# esp32-gps-eth-v12exp.net
KiCad netlist of a schematic drawn in EAGLE
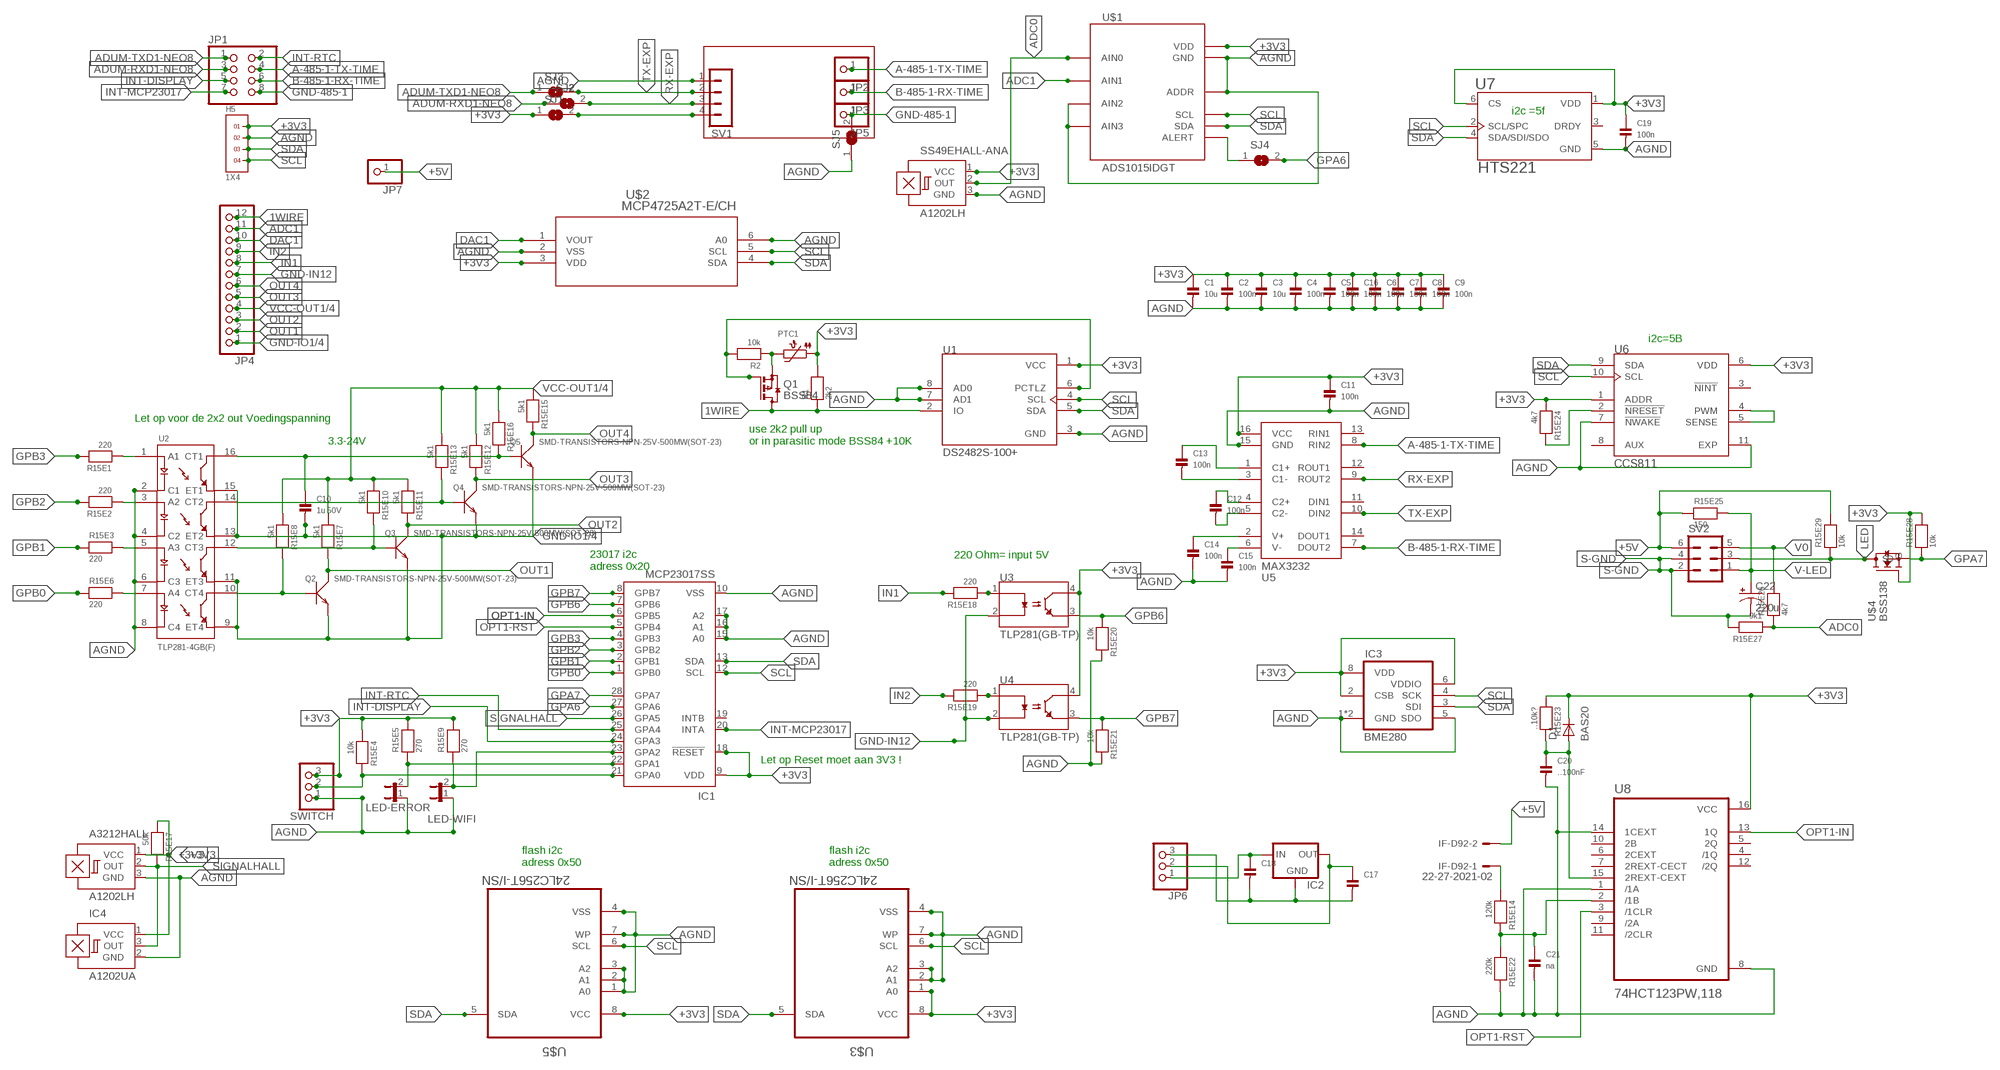
[diagram p0: schematic, sheet 1]

(export (version "E")
  (design (tool "Eeschema 10.0.6"))
  (components
    (comp (ref "A3212HALL")
      (value "A1202LH")
      (footprint "eagle-import:SOT23-W")
      (libsource (lib "eagle-import") (part "A12?LH02"))
    )
    (comp (ref "C1")
      (value "10u")
      (footprint "eagle-import:0805")
      (libsource (lib "eagle-import") (part "CAP_CERAMIC0805"))
    )
    (comp (ref "C2")
      (value "100n")
      (footprint "eagle-import:0805")
      (libsource (lib "eagle-import") (part "CAP_CERAMIC0805"))
    )
    (comp (ref "C3")
      (value "10u")
      (footprint "eagle-import:0805")
      (libsource (lib "eagle-import") (part "CAP_CERAMIC0805"))
    )
    (comp (ref "C4")
      (value "100n")
      (footprint "eagle-import:0805")
      (libsource (lib "eagle-import") (part "CAP_CERAMIC0805"))
    )
    (comp (ref "C5")
      (value "100n")
      (footprint "eagle-import:0805")
      (libsource (lib "eagle-import") (part "CAP_CERAMIC0805"))
    )
    (comp (ref "C6")
      (value "100n")
      (footprint "eagle-import:0805")
      (libsource (lib "eagle-import") (part "CAP_CERAMIC0805"))
    )
    (comp (ref "C7")
      (value "100n")
      (footprint "eagle-import:0805")
      (libsource (lib "eagle-import") (part "CAP_CERAMIC0805"))
    )
    (comp (ref "C8")
      (value "100n")
      (footprint "eagle-import:0805")
      (libsource (lib "eagle-import") (part "CAP_CERAMIC0805"))
    )
    (comp (ref "C9")
      (value "100n")
      (footprint "eagle-import:0805")
      (libsource (lib "eagle-import") (part "CAP_CERAMIC0805"))
    )
    (comp (ref "C10")
      (value "1u 50V")
      (footprint "eagle-import:0805")
      (libsource (lib "eagle-import") (part "CAP_CERAMIC0805"))
    )
    (comp (ref "C11")
      (value "100n")
      (footprint "eagle-import:0805")
      (libsource (lib "eagle-import") (part "CAP_CERAMIC0805"))
    )
    (comp (ref "C12")
      (value "100n")
      (footprint "eagle-import:0805")
      (libsource (lib "eagle-import") (part "CAP_CERAMIC0805"))
    )
    (comp (ref "C13")
      (value "100n")
      (footprint "eagle-import:0805")
      (libsource (lib "eagle-import") (part "CAP_CERAMIC0805"))
    )
    (comp (ref "C14")
      (value "100n")
      (footprint "eagle-import:0805")
      (libsource (lib "eagle-import") (part "CAP_CERAMIC0805"))
    )
    (comp (ref "C15")
      (value "100n")
      (footprint "eagle-import:0805")
      (libsource (lib "eagle-import") (part "CAP_CERAMIC0805"))
    )
    (comp (ref "C16")
      (value "100n")
      (footprint "eagle-import:0805")
      (libsource (lib "eagle-import") (part "CAP_CERAMIC0805"))
    )
    (comp (ref "C17")
      (value "CAP_CERAMIC0805")
      (footprint "eagle-import:0805")
      (libsource (lib "eagle-import") (part "CAP_CERAMIC0805"))
    )
    (comp (ref "C18")
      (value "CAP_CERAMIC0805")
      (footprint "eagle-import:0805")
      (libsource (lib "eagle-import") (part "CAP_CERAMIC0805"))
    )
    (comp (ref "C19")
      (value "100n")
      (footprint "eagle-import:0805")
      (libsource (lib "eagle-import") (part "CAP_CERAMIC0805"))
    )
    (comp (ref "C20")
      (value "..100nF")
      (footprint "eagle-import:0805")
      (libsource (lib "eagle-import") (part "CAP_CERAMIC0805"))
    )
    (comp (ref "C21")
      (value "na")
      (footprint "eagle-import:0805")
      (libsource (lib "eagle-import") (part "CAP_CERAMIC0805"))
    )
    (comp (ref "C22")
      (value "220u")
      (footprint "eagle-import:153CLV-0605")
      (libsource (lib "eagle-import") (part "CPOL-US153CLV-0605"))
    )
    (comp (ref "D1")
      (value "BAS20")
      (footprint "eagle-import:SOT23")
      (fields (field (name "MF") "ON Semiconductor"))
      (libsource (lib "eagle-import") (part "BAS20"))
    )
    (comp (ref "H5")
      (value "1X4")
      (footprint "eagle-import:1X4")
      (libsource (lib "eagle-import") (part "1X4"))
    )
    (comp (ref "IC1")
      (value "MCP23017SS")
      (footprint "eagle-import:SSOP28")
      (fields (field (name "MF") "MICROCHIP") (field (name "MPN") "MCP23017-E/SS"))
      (libsource (lib "eagle-import") (part "MCP23017SS"))
    )
    (comp (ref "IC2")
      (value "LM1117TO263")
      (footprint "eagle-import:TO263")
      (libsource (lib "eagle-import") (part "LM1117TO263"))
    )
    (comp (ref "IC3")
      (value "BME280")
      (footprint "eagle-import:BME280")
      (libsource (lib "eagle-import") (part "BME280"))
    )
    (comp (ref "IC4")
      (value "A1202UA")
      (footprint "eagle-import:SIP3-UA")
      (libsource (lib "eagle-import") (part "A12?UA02"))
    )
    (comp (ref "IF-D92")
      (value "22-27-2021-02")
      (footprint "eagle-import:6410-02")
      (libsource (lib "eagle-import") (part "22-?-0227-2021"))
    )
    (comp (ref "JP1")
      (value "PINHD-2X4")
      (footprint "eagle-import:2X04")
      (libsource (lib "eagle-import") (part "PINHD-2X4"))
    )
    (comp (ref "JP2")
      (value "PINHD-1X1")
      (footprint "eagle-import:1X01")
      (libsource (lib "eagle-import") (part "PINHD-1X1"))
    )
    (comp (ref "JP3")
      (value "PINHD-1X1")
      (footprint "eagle-import:1X01")
      (libsource (lib "eagle-import") (part "PINHD-1X1"))
    )
    (comp (ref "JP4")
      (value "PINHD-1X12")
      (footprint "eagle-import:1X12")
      (libsource (lib "eagle-import") (part "PINHD-1X12"))
    )
    (comp (ref "JP5")
      (value "PINHD-1X1")
      (footprint "eagle-import:1X01")
      (libsource (lib "eagle-import") (part "PINHD-1X1"))
    )
    (comp (ref "JP6")
      (value "PINHD-1X3")
      (footprint "eagle-import:1X03")
      (libsource (lib "eagle-import") (part "PINHD-1X3"))
    )
    (comp (ref "JP7")
      (value "PINHD-1X1")
      (footprint "eagle-import:1X01")
      (libsource (lib "eagle-import") (part "PINHD-1X1"))
    )
    (comp (ref "LED-ERROR")
      (value "JP1E")
      (footprint "eagle-import:JP1")
      (libsource (lib "eagle-import") (part "JP1E"))
    )
    (comp (ref "LED-WIFI")
      (value "JP1E")
      (footprint "eagle-import:JP1")
      (libsource (lib "eagle-import") (part "JP1E"))
    )
    (comp (ref "PTC1")
      (value "PTC1206")
      (footprint "eagle-import:1206")
      (libsource (lib "eagle-import") (part "PTC1206"))
    )
    (comp (ref "Q1")
      (value "BSS84")
      (footprint "eagle-import:SOT23")
      (libsource (lib "eagle-import") (part "BSS84"))
    )
    (comp (ref "Q2")
      (value "SMD-TRANSISTORS-NPN-25V-500MW(SOT-23)")
      (footprint "eagle-import:SOT-23")
      (fields (field (name "MF") "Micro Commercial") (field (name "MP") "S8050"))
      (libsource (lib "eagle-import") (part "SMD-TRANSISTORS-NPN-25V-500MW(SOT-23)"))
    )
    (comp (ref "Q3")
      (value "SMD-TRANSISTORS-NPN-25V-500MW(SOT-23)")
      (footprint "eagle-import:SOT-23")
      (fields (field (name "MF") "Micro Commercial") (field (name "MP") "S8050"))
      (libsource (lib "eagle-import") (part "SMD-TRANSISTORS-NPN-25V-500MW(SOT-23)"))
    )
    (comp (ref "Q4")
      (value "SMD-TRANSISTORS-NPN-25V-500MW(SOT-23)")
      (footprint "eagle-import:SOT-23")
      (fields (field (name "MF") "Micro Commercial") (field (name "MP") "S8050"))
      (libsource (lib "eagle-import") (part "SMD-TRANSISTORS-NPN-25V-500MW(SOT-23)"))
    )
    (comp (ref "Q5")
      (value "SMD-TRANSISTORS-NPN-25V-500MW(SOT-23)")
      (footprint "eagle-import:SOT-23")
      (fields (field (name "MF") "Micro Commercial") (field (name "MP") "S8050"))
      (libsource (lib "eagle-import") (part "SMD-TRANSISTORS-NPN-25V-500MW(SOT-23)"))
    )
    (comp (ref "R1")
      (value "2k2")
      (footprint "eagle-import:0805")
      (libsource (lib "eagle-import") (part "RESISTOR0805"))
    )
    (comp (ref "R2")
      (value "10k")
      (footprint "eagle-import:0805")
      (libsource (lib "eagle-import") (part "RESISTOR0805"))
    )
    (comp (ref "R15E1")
      (value "220")
      (footprint "eagle-import:_0805")
      (libsource (lib "eagle-import") (part "RESISTOR_0805"))
    )
    (comp (ref "R15E2")
      (value "220")
      (footprint "eagle-import:_0805")
      (libsource (lib "eagle-import") (part "RESISTOR_0805"))
    )
    (comp (ref "R15E3")
      (value "220")
      (footprint "eagle-import:_0805")
      (libsource (lib "eagle-import") (part "RESISTOR_0805"))
    )
    (comp (ref "R15E4")
      (value "10k")
      (footprint "eagle-import:_0805")
      (libsource (lib "eagle-import") (part "RESISTOR_0805"))
    )
    (comp (ref "R15E5")
      (value "270")
      (footprint "eagle-import:_0805")
      (libsource (lib "eagle-import") (part "RESISTOR_0805"))
    )
    (comp (ref "R15E6")
      (value "220")
      (footprint "eagle-import:_0805")
      (libsource (lib "eagle-import") (part "RESISTOR_0805"))
    )
    (comp (ref "R15E7")
      (value "5k1")
      (footprint "eagle-import:_0805")
      (libsource (lib "eagle-import") (part "RESISTOR_0805"))
    )
    (comp (ref "R15E8")
      (value "5k1")
      (footprint "eagle-import:_0805")
      (libsource (lib "eagle-import") (part "RESISTOR_0805"))
    )
    (comp (ref "R15E9")
      (value "270")
      (footprint "eagle-import:_0805")
      (libsource (lib "eagle-import") (part "RESISTOR_0805"))
    )
    (comp (ref "R15E10")
      (value "5k1")
      (footprint "eagle-import:_0805")
      (libsource (lib "eagle-import") (part "RESISTOR_0805"))
    )
    (comp (ref "R15E11")
      (value "5k1")
      (footprint "eagle-import:_0805")
      (libsource (lib "eagle-import") (part "RESISTOR_0805"))
    )
    (comp (ref "R15E12")
      (value "5k1")
      (footprint "eagle-import:_0805")
      (libsource (lib "eagle-import") (part "RESISTOR_0805"))
    )
    (comp (ref "R15E13")
      (value "5k1")
      (footprint "eagle-import:_0805")
      (libsource (lib "eagle-import") (part "RESISTOR_0805"))
    )
    (comp (ref "R15E14")
      (value "120k")
      (footprint "eagle-import:_0805")
      (libsource (lib "eagle-import") (part "RESISTOR_0805"))
    )
    (comp (ref "R15E15")
      (value "5k1")
      (footprint "eagle-import:_0805")
      (libsource (lib "eagle-import") (part "RESISTOR_0805"))
    )
    (comp (ref "R15E16")
      (value "5k1")
      (footprint "eagle-import:_0805")
      (libsource (lib "eagle-import") (part "RESISTOR_0805"))
    )
    (comp (ref "R15E17")
      (value "50k")
      (footprint "eagle-import:_0805")
      (libsource (lib "eagle-import") (part "RESISTOR_0805"))
    )
    (comp (ref "R15E18")
      (value "220")
      (footprint "eagle-import:_0805")
      (libsource (lib "eagle-import") (part "RESISTOR_0805"))
    )
    (comp (ref "R15E19")
      (value "220")
      (footprint "eagle-import:_0805")
      (libsource (lib "eagle-import") (part "RESISTOR_0805"))
    )
    (comp (ref "R15E20")
      (value "10k")
      (footprint "eagle-import:_0805")
      (libsource (lib "eagle-import") (part "RESISTOR_0805"))
    )
    (comp (ref "R15E21")
      (value "10k")
      (footprint "eagle-import:_0805")
      (libsource (lib "eagle-import") (part "RESISTOR_0805"))
    )
    (comp (ref "R15E22")
      (value "220k")
      (footprint "eagle-import:_0805")
      (libsource (lib "eagle-import") (part "RESISTOR_0805"))
    )
    (comp (ref "R15E23")
      (value "..10k?")
      (footprint "eagle-import:_0805")
      (libsource (lib "eagle-import") (part "RESISTOR_0805"))
    )
    (comp (ref "R15E24")
      (value "4k7")
      (footprint "eagle-import:_0805")
      (libsource (lib "eagle-import") (part "RESISTOR_0805"))
    )
    (comp (ref "R15E25")
      (value "150")
      (footprint "eagle-import:_0805")
      (libsource (lib "eagle-import") (part "RESISTOR_0805"))
    )
    (comp (ref "R15E26")
      (value "4k7")
      (footprint "eagle-import:_0805")
      (libsource (lib "eagle-import") (part "RESISTOR_0805"))
    )
    (comp (ref "R15E27")
      (value "9k1")
      (footprint "eagle-import:_0805")
      (libsource (lib "eagle-import") (part "RESISTOR_0805"))
    )
    (comp (ref "R15E28")
      (value "10k")
      (footprint "eagle-import:_0805")
      (libsource (lib "eagle-import") (part "RESISTOR_0805"))
    )
    (comp (ref "R15E29")
      (value "10k")
      (footprint "eagle-import:_0805")
      (libsource (lib "eagle-import") (part "RESISTOR_0805"))
    )
    (comp (ref "SJ1") (value "SJ") (footprint "eagle-import:SJ") (libsource (lib "eagle-import") (part "SJ")))
    (comp (ref "SJ2") (value "SJ") (footprint "eagle-import:SJ") (libsource (lib "eagle-import") (part "SJ")))
    (comp (ref "SJ3") (value "SJ") (footprint "eagle-import:SJ") (libsource (lib "eagle-import") (part "SJ")))
    (comp (ref "SJ4") (value "SJ") (footprint "eagle-import:SJ") (libsource (lib "eagle-import") (part "SJ")))
    (comp (ref "SJ5") (value "SJ") (footprint "eagle-import:SJ") (libsource (lib "eagle-import") (part "SJ")))
    (comp (ref "SS49EHALL-ANA")
      (value "A1202LH")
      (footprint "eagle-import:SOT23-W")
      (libsource (lib "eagle-import") (part "A12?LH02"))
    )
    (comp (ref "SV1")
      (value "MA04-1")
      (footprint "eagle-import:MA04-1")
      (libsource (lib "eagle-import") (part "MA04-1"))
    )
    (comp (ref "SV2")
      (value "MA03-2")
      (footprint "eagle-import:MA03-2")
      (libsource (lib "eagle-import") (part "MA03-2"))
    )
    (comp (ref "SWITCH")
      (value "PINHD-1X3")
      (footprint "eagle-import:1X03")
      (libsource (lib "eagle-import") (part "PINHD-1X3"))
    )
    (comp (ref "U$1")
      (value "ADS1015IDGT")
      (footprint "eagle-import:MSOP10_0.5")
      (fields (field (name "MF") "Texas Instruments") (field (name "MP") "ADS1015"))
      (libsource (lib "eagle-import") (part "ADS1015IDGT"))
    )
    (comp (ref "U$2")
      (value "MCP4725A2T-E/CH")
      (footprint "eagle-import:SOT-23-6_MC")
      (fields (field (name "MF") "Microchip"))
      (libsource (lib "eagle-import") (part "MCP4725A2T-E/CH"))
    )
    (comp (ref "U$3")
      (value "24LC256T-I/SN")
      (footprint "eagle-import:SOIC127P600X175-8N")
      (libsource (lib "eagle-import") (part "24LC256T-I/SN"))
    )
    (comp (ref "U$4")
      (value "BSS138")
      (footprint "eagle-import:BSS138")
      (libsource (lib "eagle-import") (part "BSS138"))
    )
    (comp (ref "U$5")
      (value "24LC256T-I/SN")
      (footprint "eagle-import:SOIC127P600X175-8N")
      (libsource (lib "eagle-import") (part "24LC256T-I/SN"))
    )
    (comp (ref "U1")
      (value "DS2482S-100+")
      (footprint "eagle-import:SOIC127P600X175-8N")
      (fields (field (name "MF") "Maxim Integrated"))
      (libsource (lib "eagle-import") (part "DS2482S-100+"))
    )
    (comp (ref "U2")
      (value "TLP281-4GB(F)")
      (footprint "eagle-import:SOIC127P700X210-16N")
      (fields (field (name "MF") "Toshiba") (field (name "MP") "TLP281-4GB_F_"))
      (libsource (lib "eagle-import") (part "TLP281-4GB(F)"))
    )
    (comp (ref "U3")
      (value "TLP281(GB-TP)")
      (footprint "eagle-import:SOIC127P700X210-4N")
      (fields (field (name "MF") "Toshiba Semiconductor") (field (name "MP") "TLP281_GB-TP_"))
      (libsource (lib "eagle-import") (part "TLP281(GB-TP)"))
    )
    (comp (ref "U4")
      (value "TLP281(GB-TP)")
      (footprint "eagle-import:SOIC127P700X210-4N")
      (fields (field (name "MF") "Toshiba Semiconductor") (field (name "MP") "TLP281_GB-TP_"))
      (libsource (lib "eagle-import") (part "TLP281(GB-TP)"))
    )
    (comp (ref "U5")
      (value "MAX3232")
      (footprint "eagle-import:SO16")
      (fields (field (name "MF") "Texas Instruments"))
      (libsource (lib "eagle-import") (part "MAX3232"))
    )
    (comp (ref "U6")
      (value "CCS811")
      (footprint "eagle-import:SON60P270X400X110-11N")
      (fields (field (name "MF") "ams"))
      (libsource (lib "eagle-import") (part "CCS811"))
    )
    (comp (ref "U7")
      (value "HTS221")
      (footprint "eagle-import:XDCR_HTS221")
      (fields (field (name "MF") "STMicroelectronics"))
      (libsource (lib "eagle-import") (part "HTS221"))
    )
    (comp (ref "U8")
      (value "74HCT123PW,118")
      (footprint "eagle-import:SOP65P640X110-16N")
      (fields (field (name "MF") "Nexperia USA"))
      (libsource (lib "eagle-import") (part "74HCT123PW,118"))
    )
  )
  (nets
    (net (code "1") (name "+3V3") (class "Default")
      (node (ref "A3212HALL") (pin "1") (pinfunction "VCC_1") (pintype "power_in"))
      (node (ref "C1") (pin "1") (pinfunction "P$1_1") (pintype "passive"))
      (node (ref "C11") (pin "1") (pinfunction "P$1_1") (pintype "passive"))
      (node (ref "C16") (pin "1") (pinfunction "P$1_1") (pintype "passive"))
      (node (ref "C19") (pin "1") (pinfunction "P$1_1") (pintype "passive"))
      (node (ref "C2") (pin "1") (pinfunction "P$1_1") (pintype "passive"))
      (node (ref "C3") (pin "1") (pinfunction "P$1_1") (pintype "passive"))
      (node (ref "C4") (pin "1") (pinfunction "P$1_1") (pintype "passive"))
      (node (ref "C5") (pin "1") (pinfunction "P$1_1") (pintype "passive"))
      (node (ref "C6") (pin "1") (pinfunction "P$1_1") (pintype "passive"))
      (node (ref "C7") (pin "1") (pinfunction "P$1_1") (pintype "passive"))
      (node (ref "C8") (pin "1") (pinfunction "P$1_1") (pintype "passive"))
      (node (ref "C9") (pin "1") (pinfunction "P$1_1") (pintype "passive"))
      (node (ref "D1") (pin "3") (pinfunction "K_3") (pintype "passive"))
      (node (ref "H5") (pin "1") (pinfunction "1_1") (pintype "bidirectional"))
      (node (ref "IC1") (pin "18") (pinfunction "~{RESET}_18") (pintype "input"))
      (node (ref "IC1") (pin "9") (pinfunction "VDD_9") (pintype "power_in"))
      (node (ref "IC3") (pin "2") (pinfunction "CSB_2") (pintype "input"))
      (node (ref "IC3") (pin "6") (pinfunction "VDDIO_6") (pintype "power_in"))
      (node (ref "IC3") (pin "8") (pinfunction "VDD_8") (pintype "power_in"))
      (node (ref "IC4") (pin "1") (pinfunction "VCC_1") (pintype "power_in"))
      (node (ref "PTC1") (pin "1") (pinfunction "1_1") (pintype "passive"))
      (node (ref "R1") (pin "2") (pinfunction "2_2") (pintype "passive"))
      (node (ref "R15E17") (pin "1") (pinfunction "1_1") (pintype "passive"))
      (node (ref "R15E23") (pin "1") (pinfunction "1_1") (pintype "passive"))
      (node (ref "R15E24") (pin "1") (pinfunction "1_1") (pintype "passive"))
      (node (ref "R15E28") (pin "2") (pinfunction "2_2") (pintype "passive"))
      (node (ref "R15E4") (pin "1") (pinfunction "1_1") (pintype "passive"))
      (node (ref "R15E5") (pin "2") (pinfunction "2_2") (pintype "passive"))
      (node (ref "R15E9") (pin "2") (pinfunction "2_2") (pintype "passive"))
      (node (ref "SJ1") (pin "1") (pinfunction "1_1") (pintype "passive"))
      (node (ref "SS49EHALL-ANA") (pin "1") (pinfunction "VCC_1") (pintype "power_in"))
      (node (ref "SWITCH") (pin "3") (pinfunction "3_3") (pintype "passive"))
      (node (ref "U$1") (pin "8") (pinfunction "VDD_8") (pintype "power_in"))
      (node (ref "U$2") (pin "3") (pinfunction "VDD_3") (pintype "passive"))
      (node (ref "U$3") (pin "1") (pinfunction "A0_1") (pintype "input"))
      (node (ref "U$3") (pin "8") (pinfunction "VCC_8") (pintype "power_in"))
      (node (ref "U$4") (pin "G") (pinfunction "G_G") (pintype "passive"))
      (node (ref "U$5") (pin "8") (pinfunction "VCC_8") (pintype "power_in"))
      (node (ref "U1") (pin "1") (pinfunction "VCC_1") (pintype "power_in"))
      (node (ref "U3") (pin "4") (pinfunction "COLLECTOR_4") (pintype "passive"))
      (node (ref "U4") (pin "4") (pinfunction "COLLECTOR_4") (pintype "passive"))
      (node (ref "U5") (pin "16") (pinfunction "VCC_16") (pintype "passive"))
      (node (ref "U6") (pin "1") (pinfunction "ADDR_1") (pintype "input"))
      (node (ref "U6") (pin "6") (pinfunction "VDD_6") (pintype "power_in"))
      (node (ref "U7") (pin "1") (pinfunction "VDD_1") (pintype "power_in"))
      (node (ref "U7") (pin "6") (pinfunction "CS_6") (pintype "input"))
      (node (ref "U8") (pin "16") (pinfunction "VCC_16") (pintype "power_in"))
    )
    (net (code "2") (name "+5V") (class "Default")
      (node (ref "IF-D92") (pin "2") (pinfunction "S_2") (pintype "passive"))
      (node (ref "JP7") (pin "1") (pinfunction "1_1") (pintype "passive"))
      (node (ref "R15E25") (pin "1") (pinfunction "1_1") (pintype "passive"))
      (node (ref "R15E29") (pin "2") (pinfunction "2_2") (pintype "passive"))
      (node (ref "SV2") (pin "6") (pinfunction "6_6") (pintype "passive"))
    )
    (net (code "3") (name "1WIRE") (class "Default")
      (node (ref "JP4") (pin "12") (pinfunction "12_12") (pintype "passive"))
      (node (ref "Q1") (pin "3") (pinfunction "D_3") (pintype "passive"))
      (node (ref "R1") (pin "1") (pinfunction "1_1") (pintype "passive"))
      (node (ref "U1") (pin "2") (pinfunction "IO_2") (pintype "bidirectional"))
    )
    (net (code "4") (name "A-485-1-TX-TIME") (class "Default")
      (node (ref "JP1") (pin "4") (pinfunction "4_4") (pintype "passive"))
      (node (ref "JP2") (pin "1") (pinfunction "1_1") (pintype "passive"))
      (node (ref "U5") (pin "8") (pinfunction "RIN2_8") (pintype "input"))
    )
    (net (code "5") (name "ADC0") (class "Default")
      (node (ref "R15E26") (pin "1") (pinfunction "1_1") (pintype "passive"))
      (node (ref "R15E27") (pin "1") (pinfunction "1_1") (pintype "passive"))
      (node (ref "SS49EHALL-ANA") (pin "2") (pinfunction "OUT_2") (pintype "output"))
      (node (ref "U$1") (pin "4") (pinfunction "AIN0_4") (pintype "input"))
    )
    (net (code "6") (name "ADC1") (class "Default")
      (node (ref "JP4") (pin "11") (pinfunction "11_11") (pintype "passive"))
      (node (ref "U$1") (pin "5") (pinfunction "AIN1_5") (pintype "input"))
    )
    (net (code "7") (name "ADUM-RXD1-NEO8") (class "Default")
      (node (ref "JP1") (pin "3") (pinfunction "3_3") (pintype "passive"))
      (node (ref "SJ2") (pin "1") (pinfunction "1_1") (pintype "passive"))
    )
    (net (code "8") (name "ADUM-TXD1-NEO8") (class "Default")
      (node (ref "JP1") (pin "1") (pinfunction "1_1") (pintype "passive"))
      (node (ref "SJ3") (pin "1") (pinfunction "1_1") (pintype "passive"))
    )
    (net (code "9") (name "AGND") (class "Default")
      (node (ref "A3212HALL") (pin "3") (pinfunction "GND_3") (pintype "power_in"))
      (node (ref "C1") (pin "2") (pinfunction "P$2_2") (pintype "passive"))
      (node (ref "C11") (pin "2") (pinfunction "P$2_2") (pintype "passive"))
      (node (ref "C14") (pin "2") (pinfunction "P$2_2") (pintype "passive"))
      (node (ref "C15") (pin "2") (pinfunction "P$2_2") (pintype "passive"))
      (node (ref "C16") (pin "2") (pinfunction "P$2_2") (pintype "passive"))
      (node (ref "C19") (pin "2") (pinfunction "P$2_2") (pintype "passive"))
      (node (ref "C2") (pin "2") (pinfunction "P$2_2") (pintype "passive"))
      (node (ref "C20") (pin "2") (pinfunction "P$2_2") (pintype "passive"))
      (node (ref "C21") (pin "2") (pinfunction "P$2_2") (pintype "passive"))
      (node (ref "C3") (pin "2") (pinfunction "P$2_2") (pintype "passive"))
      (node (ref "C4") (pin "2") (pinfunction "P$2_2") (pintype "passive"))
      (node (ref "C5") (pin "2") (pinfunction "P$2_2") (pintype "passive"))
      (node (ref "C6") (pin "2") (pinfunction "P$2_2") (pintype "passive"))
      (node (ref "C7") (pin "2") (pinfunction "P$2_2") (pintype "passive"))
      (node (ref "C8") (pin "2") (pinfunction "P$2_2") (pintype "passive"))
      (node (ref "C9") (pin "2") (pinfunction "P$2_2") (pintype "passive"))
      (node (ref "H5") (pin "2") (pinfunction "2_2") (pintype "bidirectional"))
      (node (ref "IC1") (pin "10") (pinfunction "VSS_10") (pintype "power_in"))
      (node (ref "IC1") (pin "15") (pinfunction "A0_15") (pintype "input"))
      (node (ref "IC1") (pin "16") (pinfunction "A1_16") (pintype "input"))
      (node (ref "IC1") (pin "17") (pinfunction "A2_17") (pintype "input"))
      (node (ref "IC3") (pin "1") (pinfunction "GND_1") (pintype "power_in"))
      (node (ref "IC3") (pin "5") (pinfunction "SDO_5") (pintype "input"))
      (node (ref "IC3") (pin "7") (pinfunction "GND_7") (pintype "power_in"))
      (node (ref "IC4") (pin "2") (pinfunction "GND_2") (pintype "power_in"))
      (node (ref "LED-ERROR") (pin "1") (pinfunction "1_1") (pintype "passive"))
      (node (ref "LED-WIFI") (pin "1") (pinfunction "1_1") (pintype "passive"))
      (node (ref "R15E20") (pin "2") (pinfunction "2_2") (pintype "passive"))
      (node (ref "R15E21") (pin "2") (pinfunction "2_2") (pintype "passive"))
      (node (ref "R15E22") (pin "2") (pinfunction "2_2") (pintype "passive"))
      (node (ref "SJ5") (pin "1") (pinfunction "1_1") (pintype "passive"))
      (node (ref "SS49EHALL-ANA") (pin "3") (pinfunction "GND_3") (pintype "power_in"))
      (node (ref "SV1") (pin "1") (pinfunction "1_1") (pintype "passive"))
      (node (ref "SWITCH") (pin "1") (pinfunction "1_1") (pintype "passive"))
      (node (ref "U$1") (pin "1") (pinfunction "ADDR_1") (pintype "input"))
      (node (ref "U$1") (pin "3") (pinfunction "GND_3") (pintype "power_in"))
      (node (ref "U$1") (pin "6") (pinfunction "AIN2_6") (pintype "input"))
      (node (ref "U$1") (pin "7") (pinfunction "AIN3_7") (pintype "input"))
      (node (ref "U$2") (pin "2") (pinfunction "VSS_2") (pintype "passive"))
      (node (ref "U$2") (pin "6") (pinfunction "A0_6") (pintype "passive"))
      (node (ref "U$3") (pin "2") (pinfunction "A1_2") (pintype "input"))
      (node (ref "U$3") (pin "3") (pinfunction "A2_3") (pintype "input"))
      (node (ref "U$3") (pin "4") (pinfunction "VSS_4") (pintype "passive"))
      (node (ref "U$3") (pin "7") (pinfunction "WP_7") (pintype "input"))
      (node (ref "U$5") (pin "1") (pinfunction "A0_1") (pintype "input"))
      (node (ref "U$5") (pin "2") (pinfunction "A1_2") (pintype "input"))
      (node (ref "U$5") (pin "3") (pinfunction "A2_3") (pintype "input"))
      (node (ref "U$5") (pin "4") (pinfunction "VSS_4") (pintype "passive"))
      (node (ref "U$5") (pin "7") (pinfunction "WP_7") (pintype "input"))
      (node (ref "U1") (pin "3") (pinfunction "GND_3") (pintype "power_in"))
      (node (ref "U1") (pin "7") (pinfunction "AD1_7") (pintype "input"))
      (node (ref "U1") (pin "8") (pinfunction "AD0_8") (pintype "input"))
      (node (ref "U2") (pin "2") (pinfunction "C1_2") (pintype "passive"))
      (node (ref "U2") (pin "4") (pinfunction "C2_4") (pintype "passive"))
      (node (ref "U2") (pin "6") (pinfunction "C3_6") (pintype "passive"))
      (node (ref "U2") (pin "8") (pinfunction "C4_8") (pintype "passive"))
      (node (ref "U5") (pin "15") (pinfunction "GND_15") (pintype "passive"))
      (node (ref "U6") (pin "11") (pinfunction "EXP_11") (pintype "power_in"))
      (node (ref "U6") (pin "7") (pinfunction "~{NWAKE}_7") (pintype "input"))
      (node (ref "U7") (pin "5") (pinfunction "GND_5") (pintype "power_in"))
      (node (ref "U8") (pin "1") (pinfunction "/1A_1") (pintype "input"))
      (node (ref "U8") (pin "14") (pinfunction "1CEXT_14") (pintype "input"))
      (node (ref "U8") (pin "8") (pinfunction "GND_8") (pintype "power_in"))
    )
    (net (code "10") (name "B-485-1-RX-TIME") (class "Default")
      (node (ref "JP1") (pin "6") (pinfunction "6_6") (pintype "passive"))
      (node (ref "JP3") (pin "1") (pinfunction "1_1") (pintype "passive"))
      (node (ref "U5") (pin "7") (pinfunction "DOUT2_7") (pintype "output"))
    )
    (net (code "11") (name "DAC1") (class "Default")
      (node (ref "JP4") (pin "10") (pinfunction "10_10") (pintype "passive"))
      (node (ref "U$2") (pin "1") (pinfunction "VOUT_1") (pintype "passive"))
    )
    (net (code "12") (name "GND-485-1") (class "Default")
      (node (ref "JP1") (pin "8") (pinfunction "8_8") (pintype "passive"))
      (node (ref "JP5") (pin "1") (pinfunction "1_1") (pintype "passive"))
      (node (ref "SJ5") (pin "2") (pinfunction "2_2") (pintype "passive"))
    )
    (net (code "13") (name "GND-IN12") (class "Default")
      (node (ref "JP4") (pin "7") (pinfunction "7_7") (pintype "passive"))
      (node (ref "U3") (pin "2") (pinfunction "CATHODE_2") (pintype "passive"))
      (node (ref "U4") (pin "2") (pinfunction "CATHODE_2") (pintype "passive"))
    )
    (net (code "14") (name "GND-IO1{slash}4") (class "Default")
      (node (ref "C10") (pin "2") (pinfunction "P$2_2") (pintype "passive"))
      (node (ref "JP4") (pin "1") (pinfunction "1_1") (pintype "passive"))
      (node (ref "Q2") (pin "2") (pinfunction "E_2") (pintype "passive"))
      (node (ref "Q3") (pin "2") (pinfunction "E_2") (pintype "passive"))
      (node (ref "Q4") (pin "2") (pinfunction "E_2") (pintype "passive"))
      (node (ref "Q5") (pin "2") (pinfunction "E_2") (pintype "passive"))
      (node (ref "U2") (pin "11") (pinfunction "ET3_11") (pintype "passive"))
      (node (ref "U2") (pin "13") (pinfunction "ET2_13") (pintype "passive"))
      (node (ref "U2") (pin "15") (pinfunction "ET1_15") (pintype "passive"))
      (node (ref "U2") (pin "9") (pinfunction "ET4_9") (pintype "passive"))
    )
    (net (code "15") (name "GPA6") (class "Default")
      (node (ref "IC1") (pin "27") (pinfunction "GPA6_27") (pintype "bidirectional"))
      (node (ref "SJ4") (pin "2") (pinfunction "2_2") (pintype "passive"))
    )
    (net (code "16") (name "GPA7") (class "Default")
      (node (ref "IC1") (pin "28") (pinfunction "GPA7_28") (pintype "bidirectional"))
      (node (ref "R15E28") (pin "1") (pinfunction "1_1") (pintype "passive"))
      (node (ref "U$4") (pin "S") (pinfunction "S_S") (pintype "passive"))
    )
    (net (code "17") (name "GPB0") (class "Default")
      (node (ref "IC1") (pin "1") (pinfunction "GPB0_1") (pintype "bidirectional"))
      (node (ref "R15E6") (pin "1") (pinfunction "1_1") (pintype "passive"))
    )
    (net (code "18") (name "GPB1") (class "Default")
      (node (ref "IC1") (pin "2") (pinfunction "GPB1_2") (pintype "bidirectional"))
      (node (ref "R15E3") (pin "1") (pinfunction "1_1") (pintype "passive"))
    )
    (net (code "19") (name "GPB2") (class "Default")
      (node (ref "IC1") (pin "3") (pinfunction "GPB2_3") (pintype "bidirectional"))
      (node (ref "R15E2") (pin "2") (pinfunction "2_2") (pintype "passive"))
    )
    (net (code "20") (name "GPB3") (class "Default")
      (node (ref "IC1") (pin "4") (pinfunction "GPB3_4") (pintype "bidirectional"))
      (node (ref "R15E1") (pin "2") (pinfunction "2_2") (pintype "passive"))
    )
    (net (code "21") (name "GPB6") (class "Default")
      (node (ref "IC1") (pin "7") (pinfunction "GPB6_7") (pintype "bidirectional"))
      (node (ref "R15E20") (pin "1") (pinfunction "1_1") (pintype "passive"))
      (node (ref "U3") (pin "3") (pinfunction "EMITTER_3") (pintype "passive"))
    )
    (net (code "22") (name "GPB7") (class "Default")
      (node (ref "IC1") (pin "8") (pinfunction "GPB7_8") (pintype "bidirectional"))
      (node (ref "R15E21") (pin "1") (pinfunction "1_1") (pintype "passive"))
      (node (ref "U4") (pin "3") (pinfunction "EMITTER_3") (pintype "passive"))
    )
    (net (code "23") (name "IN1") (class "Default")
      (node (ref "JP4") (pin "8") (pinfunction "8_8") (pintype "passive"))
      (node (ref "R15E18") (pin "2") (pinfunction "2_2") (pintype "passive"))
    )
    (net (code "24") (name "IN2") (class "Default")
      (node (ref "JP4") (pin "9") (pinfunction "9_9") (pintype "passive"))
      (node (ref "R15E19") (pin "2") (pinfunction "2_2") (pintype "passive"))
    )
    (net (code "25") (name "INT-DISPLAY") (class "Default")
      (node (ref "IC1") (pin "24") (pinfunction "GPA3_24") (pintype "bidirectional"))
      (node (ref "JP1") (pin "5") (pinfunction "5_5") (pintype "passive"))
    )
    (net (code "26") (name "INT-MCP23017") (class "Default")
      (node (ref "IC1") (pin "20") (pinfunction "INTA_20") (pintype "output"))
      (node (ref "JP1") (pin "7") (pinfunction "7_7") (pintype "passive"))
    )
    (net (code "27") (name "INT-RTC") (class "Default")
      (node (ref "IC1") (pin "25") (pinfunction "GPA4_25") (pintype "bidirectional"))
      (node (ref "JP1") (pin "2") (pinfunction "2_2") (pintype "passive"))
    )
    (net (code "28") (name "LED") (class "Default")
      (node (ref "R15E29") (pin "1") (pinfunction "1_1") (pintype "passive"))
      (node (ref "SV2") (pin "3") (pinfunction "3_3") (pintype "passive"))
      (node (ref "U$4") (pin "D") (pinfunction "D_D") (pintype "passive"))
    )
    (net (code "29") (name "Net-(C10-P$1)") (class "Default")
      (node (ref "C10") (pin "1") (pinfunction "P$1_1") (pintype "passive"))
      (node (ref "Q5") (pin "1") (pinfunction "B_1") (pintype "passive"))
      (node (ref "R15E16") (pin "2") (pinfunction "2_2") (pintype "passive"))
      (node (ref "U2") (pin "16") (pinfunction "CT1_16") (pintype "passive"))
    )
    (net (code "30") (name "Net-(C12-P$1)") (class "Default")
      (node (ref "C12") (pin "1") (pinfunction "P$1_1") (pintype "passive"))
      (node (ref "U5") (pin "4") (pinfunction "C2+_4") (pintype "passive"))
    )
    (net (code "31") (name "Net-(C12-P$2)") (class "Default")
      (node (ref "C12") (pin "2") (pinfunction "P$2_2") (pintype "passive"))
      (node (ref "U5") (pin "5") (pinfunction "C2-_5") (pintype "passive"))
    )
    (net (code "32") (name "Net-(C13-P$1)") (class "Default")
      (node (ref "C13") (pin "1") (pinfunction "P$1_1") (pintype "passive"))
      (node (ref "U5") (pin "1") (pinfunction "C1+_1") (pintype "passive"))
    )
    (net (code "33") (name "Net-(C13-P$2)") (class "Default")
      (node (ref "C13") (pin "2") (pinfunction "P$2_2") (pintype "passive"))
      (node (ref "U5") (pin "3") (pinfunction "C1-_3") (pintype "passive"))
    )
    (net (code "34") (name "Net-(C14-P$1)") (class "Default")
      (node (ref "C14") (pin "1") (pinfunction "P$1_1") (pintype "passive"))
      (node (ref "U5") (pin "2") (pinfunction "V+_2") (pintype "output"))
    )
    (net (code "35") (name "Net-(C15-P$1)") (class "Default")
      (node (ref "C15") (pin "1") (pinfunction "P$1_1") (pintype "passive"))
      (node (ref "U5") (pin "6") (pinfunction "V-_6") (pintype "output"))
    )
    (net (code "36") (name "Net-(C17-P$1)") (class "Default")
      (node (ref "C17") (pin "1") (pinfunction "P$1_1") (pintype "passive"))
      (node (ref "IC2") (pin "2") (pinfunction "OUT_2") (pintype "passive"))
      (node (ref "JP6") (pin "2") (pinfunction "2_2") (pintype "passive"))
    )
    (net (code "37") (name "Net-(C17-P$2)") (class "Default")
      (node (ref "C17") (pin "2") (pinfunction "P$2_2") (pintype "passive"))
      (node (ref "C18") (pin "2") (pinfunction "P$2_2") (pintype "passive"))
      (node (ref "IC2") (pin "1") (pinfunction "GND_1") (pintype "input"))
      (node (ref "JP6") (pin "3") (pinfunction "3_3") (pintype "passive"))
    )
    (net (code "38") (name "Net-(C18-P$1)") (class "Default")
      (node (ref "C18") (pin "1") (pinfunction "P$1_1") (pintype "passive"))
      (node (ref "IC2") (pin "3") (pinfunction "IN_3") (pintype "input"))
      (node (ref "JP6") (pin "1") (pinfunction "1_1") (pintype "passive"))
    )
    (net (code "39") (name "Net-(C20-P$1)") (class "Default")
      (node (ref "C20") (pin "1") (pinfunction "P$1_1") (pintype "passive"))
      (node (ref "D1") (pin "1") (pinfunction "A_1") (pintype "passive"))
      (node (ref "R15E23") (pin "2") (pinfunction "2_2") (pintype "passive"))
      (node (ref "U8") (pin "15") (pinfunction "2REXT-CEXT_15") (pintype "input"))
    )
    (net (code "40") (name "Net-(C21-P$1)") (class "Default")
      (node (ref "C21") (pin "1") (pinfunction "P$1_1") (pintype "passive"))
      (node (ref "R15E14") (pin "2") (pinfunction "2_2") (pintype "passive"))
      (node (ref "R15E22") (pin "1") (pinfunction "1_1") (pintype "passive"))
      (node (ref "U8") (pin "2") (pinfunction "/1B_2") (pintype "input"))
    )
    (net (code "41") (name "Net-(IC1-GPA0)") (class "Default")
      (node (ref "IC1") (pin "21") (pinfunction "GPA0_21") (pintype "bidirectional"))
      (node (ref "R15E4") (pin "2") (pinfunction "2_2") (pintype "passive"))
      (node (ref "SWITCH") (pin "2") (pinfunction "2_2") (pintype "passive"))
    )
    (net (code "42") (name "Net-(IC1-GPA1)") (class "Default")
      (node (ref "IC1") (pin "22") (pinfunction "GPA1_22") (pintype "bidirectional"))
      (node (ref "LED-ERROR") (pin "2") (pinfunction "2_2") (pintype "passive"))
      (node (ref "R15E5") (pin "1") (pinfunction "1_1") (pintype "passive"))
    )
    (net (code "43") (name "Net-(IC1-GPA2)") (class "Default")
      (node (ref "IC1") (pin "23") (pinfunction "GPA2_23") (pintype "bidirectional"))
      (node (ref "LED-WIFI") (pin "2") (pinfunction "2_2") (pintype "passive"))
      (node (ref "R15E9") (pin "1") (pinfunction "1_1") (pintype "passive"))
    )
    (net (code "44") (name "Net-(IF-D92A-S)") (class "Default")
      (node (ref "IF-D92") (pin "1") (pinfunction "S_1") (pintype "passive"))
      (node (ref "R15E14") (pin "1") (pinfunction "1_1") (pintype "passive"))
    )
    (net (code "45") (name "Net-(Q1-G)") (class "Default")
      (node (ref "Q1") (pin "1") (pinfunction "G_1") (pintype "passive"))
      (node (ref "R2") (pin "2") (pinfunction "2_2") (pintype "passive"))
      (node (ref "U1") (pin "6") (pinfunction "PCTLZ_6") (pintype "output"))
    )
    (net (code "46") (name "Net-(Q1-S)") (class "Default")
      (node (ref "PTC1") (pin "2") (pinfunction "2_2") (pintype "passive"))
      (node (ref "Q1") (pin "2") (pinfunction "S_2") (pintype "passive"))
      (node (ref "R2") (pin "1") (pinfunction "1_1") (pintype "passive"))
    )
    (net (code "47") (name "Net-(Q2-B)") (class "Default")
      (node (ref "Q2") (pin "1") (pinfunction "B_1") (pintype "passive"))
      (node (ref "R15E8") (pin "2") (pinfunction "2_2") (pintype "passive"))
      (node (ref "U2") (pin "10") (pinfunction "CT4_10") (pintype "passive"))
    )
    (net (code "48") (name "Net-(Q3-B)") (class "Default")
      (node (ref "Q3") (pin "1") (pinfunction "B_1") (pintype "passive"))
      (node (ref "R15E10") (pin "2") (pinfunction "2_2") (pintype "passive"))
      (node (ref "U2") (pin "12") (pinfunction "CT3_12") (pintype "passive"))
    )
    (net (code "49") (name "Net-(Q4-B)") (class "Default")
      (node (ref "Q4") (pin "1") (pinfunction "B_1") (pintype "passive"))
      (node (ref "R15E13") (pin "2") (pinfunction "2_2") (pintype "passive"))
      (node (ref "U2") (pin "14") (pinfunction "CT2_14") (pintype "passive"))
    )
    (net (code "50") (name "Net-(SJ1-Pad2)") (class "Default")
      (node (ref "SJ1") (pin "2") (pinfunction "2_2") (pintype "passive"))
      (node (ref "SV1") (pin "4") (pinfunction "4_4") (pintype "passive"))
    )
    (net (code "51") (name "Net-(U$1-ALERT)") (class "Default")
      (node (ref "SJ4") (pin "1") (pinfunction "1_1") (pintype "passive"))
      (node (ref "U$1") (pin "2") (pinfunction "ALERT_2") (pintype "output"))
    )
    (net (code "52") (name "Net-(U2-A1)") (class "Default")
      (node (ref "R15E1") (pin "1") (pinfunction "1_1") (pintype "passive"))
      (node (ref "U2") (pin "1") (pinfunction "A1_1") (pintype "passive"))
    )
    (net (code "53") (name "Net-(U2-A2)") (class "Default")
      (node (ref "R15E2") (pin "1") (pinfunction "1_1") (pintype "passive"))
      (node (ref "U2") (pin "3") (pinfunction "A2_3") (pintype "passive"))
    )
    (net (code "54") (name "Net-(U2-A3)") (class "Default")
      (node (ref "R15E3") (pin "2") (pinfunction "2_2") (pintype "passive"))
      (node (ref "U2") (pin "5") (pinfunction "A3_5") (pintype "passive"))
    )
    (net (code "55") (name "Net-(U2-A4)") (class "Default")
      (node (ref "R15E6") (pin "2") (pinfunction "2_2") (pintype "passive"))
      (node (ref "U2") (pin "7") (pinfunction "A4_7") (pintype "passive"))
    )
    (net (code "56") (name "Net-(U3-ANODE)") (class "Default")
      (node (ref "R15E18") (pin "1") (pinfunction "1_1") (pintype "passive"))
      (node (ref "U3") (pin "1") (pinfunction "ANODE_1") (pintype "passive"))
    )
    (net (code "57") (name "Net-(U4-ANODE)") (class "Default")
      (node (ref "R15E19") (pin "1") (pinfunction "1_1") (pintype "passive"))
      (node (ref "U4") (pin "1") (pinfunction "ANODE_1") (pintype "passive"))
    )
    (net (code "58") (name "Net-(U6-PWM)") (class "Default")
      (node (ref "U6") (pin "4") (pinfunction "PWM_4") (pintype "output"))
      (node (ref "U6") (pin "5") (pinfunction "SENSE_5") (pintype "input"))
    )
    (net (code "59") (name "Net-(U6-~{NRESET})") (class "Default")
      (node (ref "R15E24") (pin "2") (pinfunction "2_2") (pintype "passive"))
      (node (ref "U6") (pin "2") (pinfunction "~{NRESET}_2") (pintype "input"))
    )
    (net (code "60") (name "OPT1-IN") (class "Default")
      (node (ref "IC1") (pin "6") (pinfunction "GPB5_6") (pintype "bidirectional"))
      (node (ref "U8") (pin "13") (pinfunction "1Q_13") (pintype "output"))
    )
    (net (code "61") (name "OPT1-RST") (class "Default")
      (node (ref "IC1") (pin "5") (pinfunction "GPB4_5") (pintype "bidirectional"))
      (node (ref "U8") (pin "3") (pinfunction "/1CLR_3") (pintype "input"))
    )
    (net (code "62") (name "OUT1") (class "Default")
      (node (ref "JP4") (pin "2") (pinfunction "2_2") (pintype "passive"))
      (node (ref "Q2") (pin "3") (pinfunction "C_3") (pintype "passive"))
      (node (ref "R15E7") (pin "2") (pinfunction "2_2") (pintype "passive"))
    )
    (net (code "63") (name "OUT2") (class "Default")
      (node (ref "JP4") (pin "3") (pinfunction "3_3") (pintype "passive"))
      (node (ref "Q3") (pin "3") (pinfunction "C_3") (pintype "passive"))
      (node (ref "R15E11") (pin "2") (pinfunction "2_2") (pintype "passive"))
    )
    (net (code "64") (name "OUT3") (class "Default")
      (node (ref "JP4") (pin "5") (pinfunction "5_5") (pintype "passive"))
      (node (ref "Q4") (pin "3") (pinfunction "C_3") (pintype "passive"))
      (node (ref "R15E12") (pin "2") (pinfunction "2_2") (pintype "passive"))
    )
    (net (code "65") (name "OUT4") (class "Default")
      (node (ref "JP4") (pin "6") (pinfunction "6_6") (pintype "passive"))
      (node (ref "Q5") (pin "3") (pinfunction "C_3") (pintype "passive"))
      (node (ref "R15E15") (pin "2") (pinfunction "2_2") (pintype "passive"))
    )
    (net (code "66") (name "RX-EXP") (class "Default")
      (node (ref "SJ2") (pin "2") (pinfunction "2_2") (pintype "passive"))
      (node (ref "SV1") (pin "3") (pinfunction "3_3") (pintype "passive"))
      (node (ref "U5") (pin "9") (pinfunction "ROUT2_9") (pintype "output"))
    )
    (net (code "67") (name "S-GND") (class "Default")
      (node (ref "C22") (pin "-") (pinfunction "-_-") (pintype "passive"))
      (node (ref "R15E27") (pin "2") (pinfunction "2_2") (pintype "passive"))
      (node (ref "SV2") (pin "2") (pinfunction "2_2") (pintype "passive"))
      (node (ref "SV2") (pin "4") (pinfunction "4_4") (pintype "passive"))
    )
    (net (code "68") (name "SCL") (class "Default")
      (node (ref "H5") (pin "4") (pinfunction "4_4") (pintype "bidirectional"))
      (node (ref "IC1") (pin "12") (pinfunction "SCL_12") (pintype "input"))
      (node (ref "IC3") (pin "4") (pinfunction "SCK_4") (pintype "bidirectional"))
      (node (ref "U$1") (pin "10") (pinfunction "SCL_10") (pintype "bidirectional"))
      (node (ref "U$2") (pin "5") (pinfunction "SCL_5") (pintype "passive"))
      (node (ref "U$3") (pin "6") (pinfunction "SCL_6") (pintype "input"))
      (node (ref "U$5") (pin "6") (pinfunction "SCL_6") (pintype "input"))
      (node (ref "U1") (pin "4") (pinfunction "SCL_4") (pintype "input"))
      (node (ref "U6") (pin "10") (pinfunction "SCL_10") (pintype "input"))
      (node (ref "U7") (pin "2") (pinfunction "SCL/SPC_2") (pintype "input"))
    )
    (net (code "69") (name "SDA") (class "Default")
      (node (ref "H5") (pin "3") (pinfunction "3_3") (pintype "bidirectional"))
      (node (ref "IC1") (pin "13") (pinfunction "SDA_13") (pintype "bidirectional"))
      (node (ref "IC3") (pin "3") (pinfunction "SDI_3") (pintype "bidirectional"))
      (node (ref "U$1") (pin "9") (pinfunction "SDA_9") (pintype "bidirectional"))
      (node (ref "U$2") (pin "4") (pinfunction "SDA_4") (pintype "passive"))
      (node (ref "U$3") (pin "5") (pinfunction "SDA_5") (pintype "bidirectional"))
      (node (ref "U$5") (pin "5") (pinfunction "SDA_5") (pintype "bidirectional"))
      (node (ref "U1") (pin "5") (pinfunction "SDA_5") (pintype "bidirectional"))
      (node (ref "U6") (pin "9") (pinfunction "SDA_9") (pintype "bidirectional"))
      (node (ref "U7") (pin "4") (pinfunction "SDA/SDI/SDO_4") (pintype "bidirectional"))
    )
    (net (code "70") (name "SIGNALHALL") (class "Default")
      (node (ref "A3212HALL") (pin "2") (pinfunction "OUT_2") (pintype "output"))
      (node (ref "IC1") (pin "26") (pinfunction "GPA5_26") (pintype "bidirectional"))
      (node (ref "IC4") (pin "3") (pinfunction "OUT_3") (pintype "output"))
      (node (ref "R15E17") (pin "2") (pinfunction "2_2") (pintype "passive"))
    )
    (net (code "71") (name "TX-EXP") (class "Default")
      (node (ref "SJ3") (pin "2") (pinfunction "2_2") (pintype "passive"))
      (node (ref "SV1") (pin "2") (pinfunction "2_2") (pintype "passive"))
      (node (ref "U5") (pin "10") (pinfunction "DIN2_10") (pintype "input"))
    )
    (net (code "72") (name "V-LED") (class "Default")
      (node (ref "C22") (pin "+") (pinfunction "+_+") (pintype "passive"))
      (node (ref "R15E25") (pin "2") (pinfunction "2_2") (pintype "passive"))
      (node (ref "SV2") (pin "1") (pinfunction "1_1") (pintype "passive"))
    )
    (net (code "73") (name "V0") (class "Default")
      (node (ref "R15E26") (pin "2") (pinfunction "2_2") (pintype "passive"))
      (node (ref "SV2") (pin "5") (pinfunction "5_5") (pintype "passive"))
    )
    (net (code "74") (name "VCC-OUT1{slash}4") (class "Default")
      (node (ref "JP4") (pin "4") (pinfunction "4_4") (pintype "passive"))
      (node (ref "R15E10") (pin "1") (pinfunction "1_1") (pintype "passive"))
      (node (ref "R15E11") (pin "1") (pinfunction "1_1") (pintype "passive"))
      (node (ref "R15E12") (pin "1") (pinfunction "1_1") (pintype "passive"))
      (node (ref "R15E13") (pin "1") (pinfunction "1_1") (pintype "passive"))
      (node (ref "R15E15") (pin "1") (pinfunction "1_1") (pintype "passive"))
      (node (ref "R15E16") (pin "1") (pinfunction "1_1") (pintype "passive"))
      (node (ref "R15E7") (pin "1") (pinfunction "1_1") (pintype "passive"))
      (node (ref "R15E8") (pin "1") (pinfunction "1_1") (pintype "passive"))
    )
    (net (code "75") (name "unconnected-(IC1-INTB-Pad19)") (class "Default")
      (node (ref "IC1") (pin "19") (pinfunction "INTB_19") (pintype "output"))
    )
    (net (code "76") (name "unconnected-(U5-DIN1-Pad11)") (class "Default")
      (node (ref "U5") (pin "11") (pinfunction "DIN1_11") (pintype "input"))
    )
    (net (code "77") (name "unconnected-(U5-DOUT1-Pad14)") (class "Default")
      (node (ref "U5") (pin "14") (pinfunction "DOUT1_14") (pintype "output"))
    )
    (net (code "78") (name "unconnected-(U5-RIN1-Pad13)") (class "Default")
      (node (ref "U5") (pin "13") (pinfunction "RIN1_13") (pintype "input"))
    )
    (net (code "79") (name "unconnected-(U5-ROUT1-Pad12)") (class "Default")
      (node (ref "U5") (pin "12") (pinfunction "ROUT1_12") (pintype "output"))
    )
    (net (code "80") (name "unconnected-(U6-AUX-Pad8)") (class "Default")
      (node (ref "U6") (pin "8") (pinfunction "AUX_8") (pintype "passive"))
    )
    (net (code "81") (name "unconnected-(U6-~{NINT}-Pad3)") (class "Default")
      (node (ref "U6") (pin "3") (pinfunction "~{NINT}_3") (pintype "output"))
    )
    (net (code "82") (name "unconnected-(U7-DRDY-Pad3)") (class "Default")
      (node (ref "U7") (pin "3") (pinfunction "DRDY_3") (pintype "output"))
    )
    (net (code "83") (name "unconnected-(U8-2B-Pad10)") (class "Default")
      (node (ref "U8") (pin "10") (pinfunction "2B_10") (pintype "input"))
    )
    (net (code "84") (name "unconnected-(U8-2CEXT-Pad6)") (class "Default")
      (node (ref "U8") (pin "6") (pinfunction "2CEXT_6") (pintype "input"))
    )
    (net (code "85") (name "unconnected-(U8-2Q-Pad5)") (class "Default")
      (node (ref "U8") (pin "5") (pinfunction "2Q_5") (pintype "output"))
    )
    (net (code "86") (name "unconnected-(U8-2REXT-CECT-Pad7)") (class "Default")
      (node (ref "U8") (pin "7") (pinfunction "2REXT-CECT_7") (pintype "input"))
    )
    (net (code "87") (name "unconnected-(U8-{slash}1Q-Pad4)") (class "Default")
      (node (ref "U8") (pin "4") (pinfunction "/1Q_4") (pintype "output"))
    )
    (net (code "88") (name "unconnected-(U8-{slash}2A-Pad9)") (class "Default")
      (node (ref "U8") (pin "9") (pinfunction "/2A_9") (pintype "input"))
    )
    (net (code "89") (name "unconnected-(U8-{slash}2CLR-Pad11)") (class "Default")
      (node (ref "U8") (pin "11") (pinfunction "/2CLR_11") (pintype "input"))
    )
    (net (code "90") (name "unconnected-(U8-{slash}2Q-Pad12)") (class "Default")
      (node (ref "U8") (pin "12") (pinfunction "/2Q_12") (pintype "output"))
    )
  )
)
